# clock.net
KiCad netlist of a schematic drawn in EAGLE
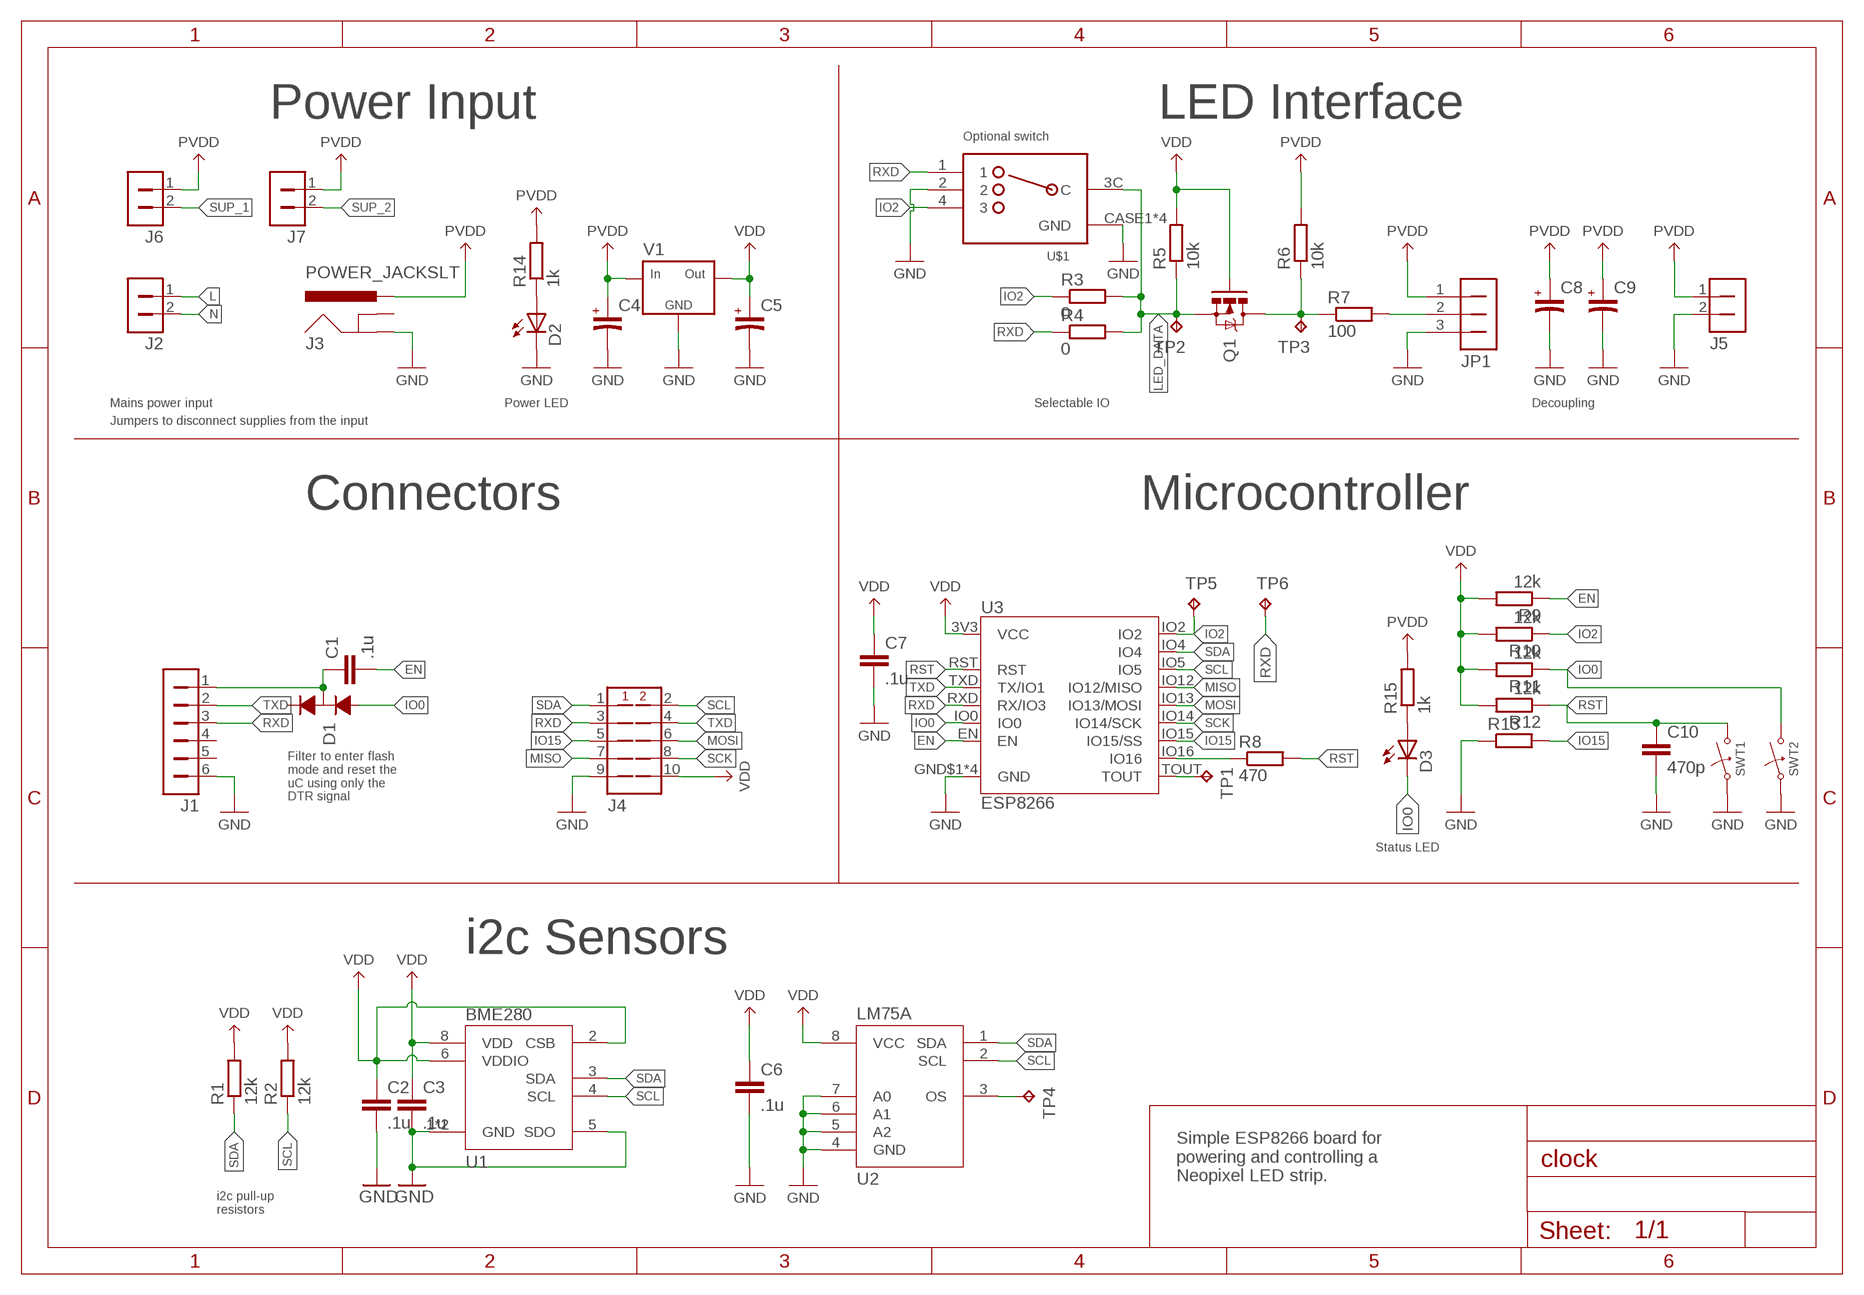
[diagram p0: schematic, sheet 1]

(export (version "E")
  (design (tool "Eeschema 10.0.6"))
  (components
    (comp (ref "C1")
      (value ".1u")
      (footprint "eagle-import:0603")
      (libsource (lib "eagle-import") (part "C_0603"))
    )
    (comp (ref "C2")
      (value ".1u")
      (footprint "eagle-import:0603")
      (libsource (lib "eagle-import") (part "C_0603"))
    )
    (comp (ref "C3")
      (value ".1u")
      (footprint "eagle-import:0603")
      (libsource (lib "eagle-import") (part "C_0603"))
    )
    (comp (ref "C4")
      (value "C_POL_1206")
      (footprint "eagle-import:1206_POL")
      (libsource (lib "eagle-import") (part "C_POL_1206"))
    )
    (comp (ref "C5")
      (value "C_POL_1206")
      (footprint "eagle-import:1206_POL")
      (libsource (lib "eagle-import") (part "C_POL_1206"))
    )
    (comp (ref "C6")
      (value ".1u")
      (footprint "eagle-import:0603")
      (libsource (lib "eagle-import") (part "C_0603"))
    )
    (comp (ref "C7")
      (value ".1u")
      (footprint "eagle-import:0603")
      (libsource (lib "eagle-import") (part "C_0603"))
    )
    (comp (ref "C8")
      (value "C_POL_AVE_X")
      (footprint "eagle-import:AVE_X")
      (libsource (lib "eagle-import") (part "C_POL_AVE_X"))
    )
    (comp (ref "C9")
      (value "C_POL_AVE_X")
      (footprint "eagle-import:AVE_X")
      (libsource (lib "eagle-import") (part "C_POL_AVE_X"))
    )
    (comp (ref "C10")
      (value "470p")
      (footprint "eagle-import:0603")
      (libsource (lib "eagle-import") (part "C_0603"))
    )
    (comp (ref "D1")
      (value "SBAV99WT1G")
      (footprint "eagle-import:SC70")
      (libsource (lib "eagle-import") (part "SBAV99WT1G"))
    )
    (comp (ref "D2")
      (value "LED_0805")
      (footprint "eagle-import:0805_LED")
      (libsource (lib "eagle-import") (part "LED_0805"))
    )
    (comp (ref "D3")
      (value "LED_0805")
      (footprint "eagle-import:0805_LED")
      (libsource (lib "eagle-import") (part "LED_0805"))
    )
    (comp (ref "J1")
      (value "1X6_RIGHT")
      (footprint "eagle-import:1X6_RIGHT")
      (libsource (lib "eagle-import") (part "1X6_RIGHT"))
    )
    (comp (ref "J2")
      (value "1X2_IEC_C8_RIGHT")
      (footprint "eagle-import:IEC_C8_RIGHT")
      (libsource (lib "eagle-import") (part "Sebastian_1X2_IEC_C8_RIGHT"))
    )
    (comp (ref "J3")
      (value "POWER_JACKSLT")
      (footprint "eagle-import:POWER_JACK_SLOT")
      (libsource (lib "eagle-import") (part "POWER_JACKSLT"))
    )
    (comp (ref "J4")
      (value "2X5")
      (footprint "eagle-import:2X5")
      (libsource (lib "eagle-import") (part "2X5"))
    )
    (comp (ref "J5")
      (value "1X2_MOLEX_53254")
      (footprint "eagle-import:1X2_MOLEX_53254")
      (libsource (lib "eagle-import") (part "Sebastian_1X2_MOLEX_53254"))
    )
    (comp (ref "J6")
      (value "1X2")
      (footprint "eagle-import:1X2")
      (libsource (lib "eagle-import") (part "1X2"))
    )
    (comp (ref "J7")
      (value "1X2")
      (footprint "eagle-import:1X2")
      (libsource (lib "eagle-import") (part "1X2"))
    )
    (comp (ref "JP1")
      (value "1X3_MOLEX_53254")
      (footprint "eagle-import:1X3_MOLEX_53254")
      (libsource (lib "eagle-import") (part "1X3_MOLEX_53254"))
    )
    (comp (ref "Q1")
      (value "NMOS_2N7002")
      (footprint "eagle-import:SOT23")
      (libsource (lib "eagle-import") (part "NMOS_2N7002"))
    )
    (comp (ref "R1")
      (value "12k")
      (footprint "eagle-import:0603")
      (libsource (lib "eagle-import") (part "R_0603"))
    )
    (comp (ref "R2")
      (value "12k")
      (footprint "eagle-import:0603")
      (libsource (lib "eagle-import") (part "R_0603"))
    )
    (comp (ref "R3")
      (value "0")
      (footprint "eagle-import:0603")
      (libsource (lib "eagle-import") (part "R_0603"))
    )
    (comp (ref "R4")
      (value "0")
      (footprint "eagle-import:0603")
      (libsource (lib "eagle-import") (part "R_0603"))
    )
    (comp (ref "R5")
      (value "10k")
      (footprint "eagle-import:0603")
      (libsource (lib "eagle-import") (part "R_0603"))
    )
    (comp (ref "R6")
      (value "10k")
      (footprint "eagle-import:0603")
      (libsource (lib "eagle-import") (part "R_0603"))
    )
    (comp (ref "R7")
      (value "100")
      (footprint "eagle-import:0603")
      (libsource (lib "eagle-import") (part "R_0603"))
    )
    (comp (ref "R8")
      (value "470")
      (footprint "eagle-import:0603")
      (libsource (lib "eagle-import") (part "R_0603"))
    )
    (comp (ref "R9")
      (value "12k")
      (footprint "eagle-import:0603")
      (libsource (lib "eagle-import") (part "R_0603"))
    )
    (comp (ref "R10")
      (value "12k")
      (footprint "eagle-import:0603")
      (libsource (lib "eagle-import") (part "R_0603"))
    )
    (comp (ref "R11")
      (value "12k")
      (footprint "eagle-import:0603")
      (libsource (lib "eagle-import") (part "R_0603"))
    )
    (comp (ref "R12")
      (value "12k")
      (footprint "eagle-import:0603")
      (libsource (lib "eagle-import") (part "R_0603"))
    )
    (comp (ref "R13")
      (value "R_0603")
      (footprint "eagle-import:0603")
      (libsource (lib "eagle-import") (part "R_0603"))
    )
    (comp (ref "R14")
      (value "1k")
      (footprint "eagle-import:0603")
      (libsource (lib "eagle-import") (part "R_0603"))
    )
    (comp (ref "R15")
      (value "1k")
      (footprint "eagle-import:0603")
      (libsource (lib "eagle-import") (part "R_0603"))
    )
    (comp (ref "SWT1")
      (value "BUTTON_SMD_2P")
      (footprint "eagle-import:BTN_SMD_2PIN")
      (libsource (lib "eagle-import") (part "BUTTON_SMD_2P"))
    )
    (comp (ref "SWT2")
      (value "BUTTON_SMD_2P")
      (footprint "eagle-import:BTN_SMD_2PIN")
      (libsource (lib "eagle-import") (part "BUTTON_SMD_2P"))
    )
    (comp (ref "TP1")
      (value "TPTP15R")
      (footprint "eagle-import:TP15R")
      (libsource (lib "eagle-import") (part "TPTP15R"))
    )
    (comp (ref "TP2")
      (value "TPTP15R")
      (footprint "eagle-import:TP15R")
      (libsource (lib "eagle-import") (part "TPTP15R"))
    )
    (comp (ref "TP3")
      (value "TPTP15R")
      (footprint "eagle-import:TP15R")
      (libsource (lib "eagle-import") (part "TPTP15R"))
    )
    (comp (ref "TP4")
      (value "TPTP15R")
      (footprint "eagle-import:TP15R")
      (libsource (lib "eagle-import") (part "TPTP15R"))
    )
    (comp (ref "TP5")
      (value "TPTP15R")
      (footprint "eagle-import:TP15R")
      (libsource (lib "eagle-import") (part "TPTP15R"))
    )
    (comp (ref "TP6")
      (value "TPTP15R")
      (footprint "eagle-import:TP15R")
      (libsource (lib "eagle-import") (part "TPTP15R"))
    )
    (comp (ref "U$1")
      (value "SWITCH_1P3T_SSSS812201")
      (footprint "eagle-import:SSSS812201")
      (libsource (lib "eagle-import") (part "SWITCH_1P3T_SSSS812201"))
    )
    (comp (ref "U1")
      (value "BME280")
      (footprint "eagle-import:BME280")
      (libsource (lib "eagle-import") (part "BME280"))
    )
    (comp (ref "U2")
      (value "LM75A_SO8")
      (footprint "eagle-import:SO8")
      (libsource (lib "eagle-import") (part "LM75A_SO8"))
    )
    (comp (ref "U3")
      (value "ESP8266_13")
      (footprint "eagle-import:ESP13")
      (libsource (lib "eagle-import") (part "ESP8266_13"))
    )
    (comp (ref "V1")
      (value "NCP1117")
      (footprint "eagle-import:TO252")
      (libsource (lib "eagle-import") (part "NCP1117"))
    )
  )
  (nets
    (net (code "1") (name "EN") (class "Default")
      (node (ref "C1") (pin "2") (pinfunction "2_2") (pintype "passive"))
      (node (ref "R9") (pin "1") (pinfunction "1_1") (pintype "passive"))
      (node (ref "U3") (pin "EN") (pinfunction "EN_EN") (pintype "bidirectional"))
    )
    (net (code "2") (name "GND") (class "Default")
      (node (ref "C10") (pin "2") (pinfunction "2_2") (pintype "passive"))
      (node (ref "C2") (pin "2") (pinfunction "2_2") (pintype "passive"))
      (node (ref "C3") (pin "2") (pinfunction "2_2") (pintype "passive"))
      (node (ref "C4") (pin "2") (pinfunction "2_2") (pintype "passive"))
      (node (ref "C5") (pin "2") (pinfunction "2_2") (pintype "passive"))
      (node (ref "C6") (pin "2") (pinfunction "2_2") (pintype "passive"))
      (node (ref "C7") (pin "2") (pinfunction "2_2") (pintype "passive"))
      (node (ref "C8") (pin "-") (pinfunction "2_-") (pintype "passive"))
      (node (ref "C9") (pin "-") (pinfunction "2_-") (pintype "passive"))
      (node (ref "D2") (pin "C") (pinfunction "C_C") (pintype "passive"))
      (node (ref "J1") (pin "6") (pinfunction "6_6") (pintype "bidirectional"))
      (node (ref "J3") (pin "GND@2") (pinfunction "GND_GND@2") (pintype "bidirectional"))
      (node (ref "J4") (pin "9") (pinfunction "9_9") (pintype "bidirectional"))
      (node (ref "J5") (pin "2") (pinfunction "2_2") (pintype "bidirectional"))
      (node (ref "JP1") (pin "3") (pinfunction "3_3") (pintype "bidirectional"))
      (node (ref "R13") (pin "1") (pinfunction "1_1") (pintype "passive"))
      (node (ref "SWT1") (pin "1") (pinfunction "P$1_1") (pintype "bidirectional"))
      (node (ref "SWT2") (pin "1") (pinfunction "P$1_1") (pintype "bidirectional"))
      (node (ref "U$1") (pin "2") (pinfunction "2_2") (pintype "bidirectional"))
      (node (ref "U$1") (pin "CASE1") (pinfunction "GND_CASE1") (pintype "bidirectional"))
      (node (ref "U$1") (pin "CASE2") (pinfunction "GND_CASE2") (pintype "bidirectional"))
      (node (ref "U$1") (pin "CASE3") (pinfunction "GND_CASE3") (pintype "bidirectional"))
      (node (ref "U$1") (pin "CASE4") (pinfunction "GND_CASE4") (pintype "bidirectional"))
      (node (ref "U1") (pin "1") (pinfunction "GND_1") (pintype "bidirectional"))
      (node (ref "U1") (pin "5") (pinfunction "SDO_5") (pintype "bidirectional"))
      (node (ref "U1") (pin "7") (pinfunction "GND_7") (pintype "bidirectional"))
      (node (ref "U2") (pin "4") (pinfunction "GND_4") (pintype "bidirectional"))
      (node (ref "U2") (pin "5") (pinfunction "A2_5") (pintype "bidirectional"))
      (node (ref "U2") (pin "6") (pinfunction "A1_6") (pintype "bidirectional"))
      (node (ref "U2") (pin "7") (pinfunction "A0_7") (pintype "bidirectional"))
      (node (ref "U3") (pin "GND$1") (pinfunction "GND_GND$1") (pintype "bidirectional"))
      (node (ref "U3") (pin "GND$2") (pinfunction "GND_GND$2") (pintype "bidirectional"))
      (node (ref "U3") (pin "GND$3") (pinfunction "GND_GND$3") (pintype "bidirectional"))
      (node (ref "U3") (pin "GND$4") (pinfunction "GND_GND$4") (pintype "bidirectional"))
      (node (ref "V1") (pin "1") (pinfunction "GND_1") (pintype "bidirectional"))
    )
    (net (code "3") (name "IO0") (class "Default")
      (node (ref "D1") (pin "1") (pinfunction "ANODE_1") (pintype "bidirectional"))
      (node (ref "D3") (pin "C") (pinfunction "C_C") (pintype "passive"))
      (node (ref "R11") (pin "1") (pinfunction "1_1") (pintype "passive"))
      (node (ref "SWT2") (pin "2") (pinfunction "P$2_2") (pintype "bidirectional"))
      (node (ref "U3") (pin "IO0") (pinfunction "IO0_IO0") (pintype "bidirectional"))
    )
    (net (code "4") (name "IO2") (class "Default")
      (node (ref "R10") (pin "1") (pinfunction "1_1") (pintype "passive"))
      (node (ref "R3") (pin "1") (pinfunction "1_1") (pintype "passive"))
      (node (ref "TP5") (pin "TP") (pinfunction "TP_TP") (pintype "input"))
      (node (ref "U$1") (pin "4") (pinfunction "3_4") (pintype "bidirectional"))
      (node (ref "U3") (pin "IO2") (pinfunction "IO2_IO2") (pintype "bidirectional"))
    )
    (net (code "5") (name "IO15") (class "Default")
      (node (ref "J4") (pin "5") (pinfunction "5_5") (pintype "bidirectional"))
      (node (ref "R13") (pin "2") (pinfunction "2_2") (pintype "passive"))
      (node (ref "U3") (pin "IO15") (pinfunction "IO15/SS_IO15") (pintype "bidirectional"))
    )
    (net (code "6") (name "L") (class "Default")
      (node (ref "J2") (pin "1") (pinfunction "1_1") (pintype "bidirectional"))
    )
    (net (code "7") (name "LED_DATA") (class "Default")
      (node (ref "Q1") (pin "2") (pinfunction "S_2") (pintype "passive"))
      (node (ref "R3") (pin "2") (pinfunction "2_2") (pintype "passive"))
      (node (ref "R4") (pin "2") (pinfunction "2_2") (pintype "passive"))
      (node (ref "R5") (pin "1") (pinfunction "1_1") (pintype "passive"))
      (node (ref "TP2") (pin "TP") (pinfunction "TP_TP") (pintype "input"))
      (node (ref "U$1") (pin "3C") (pinfunction "C_3C") (pintype "bidirectional"))
    )
    (net (code "8") (name "MISO") (class "Default")
      (node (ref "J4") (pin "7") (pinfunction "7_7") (pintype "bidirectional"))
      (node (ref "U3") (pin "IO12") (pinfunction "IO12/MISO_IO12") (pintype "bidirectional"))
    )
    (net (code "9") (name "MOSI") (class "Default")
      (node (ref "J4") (pin "6") (pinfunction "6_6") (pintype "bidirectional"))
      (node (ref "U3") (pin "IO13") (pinfunction "IO13/MOSI_IO13") (pintype "bidirectional"))
    )
    (net (code "10") (name "N") (class "Default")
      (node (ref "J2") (pin "2") (pinfunction "2_2") (pintype "bidirectional"))
    )
    (net (code "11") (name "Net-(D1-MIDDLE)") (class "Default")
      (node (ref "C1") (pin "1") (pinfunction "1_1") (pintype "passive"))
      (node (ref "D1") (pin "3") (pinfunction "MIDDLE_3") (pintype "bidirectional"))
      (node (ref "J1") (pin "1") (pinfunction "1_1") (pintype "bidirectional"))
    )
    (net (code "12") (name "Net-(D2-PadA)") (class "Default")
      (node (ref "D2") (pin "A") (pinfunction "A_A") (pintype "passive"))
      (node (ref "R14") (pin "1") (pinfunction "1_1") (pintype "passive"))
    )
    (net (code "13") (name "Net-(D3-PadA)") (class "Default")
      (node (ref "D3") (pin "A") (pinfunction "A_A") (pintype "passive"))
      (node (ref "R15") (pin "1") (pinfunction "1_1") (pintype "passive"))
    )
    (net (code "14") (name "Net-(JP1-Pad2)") (class "Default")
      (node (ref "JP1") (pin "2") (pinfunction "2_2") (pintype "bidirectional"))
      (node (ref "R7") (pin "2") (pinfunction "2_2") (pintype "passive"))
    )
    (net (code "15") (name "Net-(Q1-D)") (class "Default")
      (node (ref "Q1") (pin "3") (pinfunction "D_3") (pintype "passive"))
      (node (ref "R6") (pin "1") (pinfunction "1_1") (pintype "passive"))
      (node (ref "R7") (pin "1") (pinfunction "1_1") (pintype "passive"))
      (node (ref "TP3") (pin "TP") (pinfunction "TP_TP") (pintype "input"))
    )
    (net (code "16") (name "Net-(R8-Pad1)") (class "Default")
      (node (ref "R8") (pin "1") (pinfunction "1_1") (pintype "passive"))
      (node (ref "U3") (pin "IO16") (pinfunction "IO16_IO16") (pintype "bidirectional"))
    )
    (net (code "17") (name "Net-(TP1-PadTP)") (class "Default")
      (node (ref "TP1") (pin "TP") (pinfunction "TP_TP") (pintype "input"))
      (node (ref "U3") (pin "TOUT") (pinfunction "TOUT_TOUT") (pintype "bidirectional"))
    )
    (net (code "18") (name "Net-(U2-OS)") (class "Default")
      (node (ref "TP4") (pin "TP") (pinfunction "TP_TP") (pintype "input"))
      (node (ref "U2") (pin "3") (pinfunction "OS_3") (pintype "bidirectional"))
    )
    (net (code "19") (name "PVDD") (class "Default")
      (node (ref "C4") (pin "1") (pinfunction "1_1") (pintype "passive"))
      (node (ref "C8") (pin "+") (pinfunction "1_+") (pintype "passive"))
      (node (ref "C9") (pin "+") (pinfunction "1_+") (pintype "passive"))
      (node (ref "J3") (pin "PWR") (pinfunction "PWR_PWR") (pintype "bidirectional"))
      (node (ref "J5") (pin "1") (pinfunction "1_1") (pintype "bidirectional"))
      (node (ref "J6") (pin "1") (pinfunction "1_1") (pintype "bidirectional"))
      (node (ref "J7") (pin "1") (pinfunction "1_1") (pintype "bidirectional"))
      (node (ref "JP1") (pin "1") (pinfunction "1_1") (pintype "bidirectional"))
      (node (ref "R14") (pin "2") (pinfunction "2_2") (pintype "passive"))
      (node (ref "R15") (pin "2") (pinfunction "2_2") (pintype "passive"))
      (node (ref "R6") (pin "2") (pinfunction "2_2") (pintype "passive"))
      (node (ref "V1") (pin "2") (pinfunction "IN_2") (pintype "bidirectional"))
    )
    (net (code "20") (name "RST") (class "Default")
      (node (ref "C10") (pin "1") (pinfunction "1_1") (pintype "passive"))
      (node (ref "R12") (pin "1") (pinfunction "1_1") (pintype "passive"))
      (node (ref "R8") (pin "2") (pinfunction "2_2") (pintype "passive"))
      (node (ref "SWT1") (pin "2") (pinfunction "P$2_2") (pintype "bidirectional"))
      (node (ref "U3") (pin "RST") (pinfunction "RST_RST") (pintype "bidirectional"))
    )
    (net (code "21") (name "RXD") (class "Default")
      (node (ref "J1") (pin "3") (pinfunction "3_3") (pintype "bidirectional"))
      (node (ref "J4") (pin "3") (pinfunction "3_3") (pintype "bidirectional"))
      (node (ref "R4") (pin "1") (pinfunction "1_1") (pintype "passive"))
      (node (ref "TP6") (pin "TP") (pinfunction "TP_TP") (pintype "input"))
      (node (ref "U$1") (pin "1") (pinfunction "1_1") (pintype "bidirectional"))
      (node (ref "U3") (pin "RXD") (pinfunction "RX/IO3_RXD") (pintype "bidirectional"))
    )
    (net (code "22") (name "SCK") (class "Default")
      (node (ref "J4") (pin "8") (pinfunction "8_8") (pintype "bidirectional"))
      (node (ref "U3") (pin "IO14") (pinfunction "IO14/SCK_IO14") (pintype "bidirectional"))
    )
    (net (code "23") (name "SCL") (class "Default")
      (node (ref "J4") (pin "2") (pinfunction "2_2") (pintype "bidirectional"))
      (node (ref "R2") (pin "1") (pinfunction "1_1") (pintype "passive"))
      (node (ref "U1") (pin "4") (pinfunction "SCL_4") (pintype "bidirectional"))
      (node (ref "U2") (pin "2") (pinfunction "SCL_2") (pintype "bidirectional"))
      (node (ref "U3") (pin "IO5") (pinfunction "IO5_IO5") (pintype "bidirectional"))
    )
    (net (code "24") (name "SDA") (class "Default")
      (node (ref "J4") (pin "1") (pinfunction "1_1") (pintype "bidirectional"))
      (node (ref "R1") (pin "1") (pinfunction "1_1") (pintype "passive"))
      (node (ref "U1") (pin "3") (pinfunction "SDA_3") (pintype "bidirectional"))
      (node (ref "U2") (pin "1") (pinfunction "SDA_1") (pintype "bidirectional"))
      (node (ref "U3") (pin "IO4") (pinfunction "IO4_IO4") (pintype "bidirectional"))
    )
    (net (code "25") (name "SUP_1") (class "Default")
      (node (ref "J6") (pin "2") (pinfunction "2_2") (pintype "bidirectional"))
    )
    (net (code "26") (name "SUP_2") (class "Default")
      (node (ref "J7") (pin "2") (pinfunction "2_2") (pintype "bidirectional"))
    )
    (net (code "27") (name "TXD") (class "Default")
      (node (ref "J1") (pin "2") (pinfunction "2_2") (pintype "bidirectional"))
      (node (ref "J4") (pin "4") (pinfunction "4_4") (pintype "bidirectional"))
      (node (ref "U3") (pin "TXD") (pinfunction "TX/IO1_TXD") (pintype "bidirectional"))
    )
    (net (code "28") (name "VDD") (class "Default")
      (node (ref "C2") (pin "1") (pinfunction "1_1") (pintype "passive"))
      (node (ref "C3") (pin "1") (pinfunction "1_1") (pintype "passive"))
      (node (ref "C5") (pin "1") (pinfunction "1_1") (pintype "passive"))
      (node (ref "C6") (pin "1") (pinfunction "1_1") (pintype "passive"))
      (node (ref "C7") (pin "1") (pinfunction "1_1") (pintype "passive"))
      (node (ref "J4") (pin "10") (pinfunction "10_10") (pintype "bidirectional"))
      (node (ref "Q1") (pin "1") (pinfunction "G_1") (pintype "passive"))
      (node (ref "R1") (pin "2") (pinfunction "2_2") (pintype "passive"))
      (node (ref "R10") (pin "2") (pinfunction "2_2") (pintype "passive"))
      (node (ref "R11") (pin "2") (pinfunction "2_2") (pintype "passive"))
      (node (ref "R12") (pin "2") (pinfunction "2_2") (pintype "passive"))
      (node (ref "R2") (pin "2") (pinfunction "2_2") (pintype "passive"))
      (node (ref "R5") (pin "2") (pinfunction "2_2") (pintype "passive"))
      (node (ref "R9") (pin "2") (pinfunction "2_2") (pintype "passive"))
      (node (ref "U1") (pin "2") (pinfunction "CSB_2") (pintype "bidirectional"))
      (node (ref "U1") (pin "6") (pinfunction "VDDIO_6") (pintype "bidirectional"))
      (node (ref "U1") (pin "8") (pinfunction "VDD_8") (pintype "bidirectional"))
      (node (ref "U2") (pin "8") (pinfunction "VCC_8") (pintype "bidirectional"))
      (node (ref "U3") (pin "3V3") (pinfunction "VCC_3V3") (pintype "bidirectional"))
      (node (ref "V1") (pin "3") (pinfunction "OUT_3") (pintype "bidirectional"))
    )
    (net (code "29") (name "unconnected-(D1-CATHODE-Pad2)") (class "Default")
      (node (ref "D1") (pin "2") (pinfunction "CATHODE_2") (pintype "bidirectional"))
    )
    (net (code "30") (name "unconnected-(J1-Pad4)") (class "Default")
      (node (ref "J1") (pin "4") (pinfunction "4_4") (pintype "bidirectional"))
    )
    (net (code "31") (name "unconnected-(J1-Pad5)") (class "Default")
      (node (ref "J1") (pin "5") (pinfunction "5_5") (pintype "bidirectional"))
    )
    (net (code "32") (name "unconnected-(J3-GNDBREAK-PadGND@1)") (class "Default")
      (node (ref "J3") (pin "GND@1") (pinfunction "GNDBREAK_GND@1") (pintype "bidirectional"))
    )
  )
)
